# SCH_New-Project_2024-09-05.net
KiCad netlist of a schematic drawn in EasyEDA
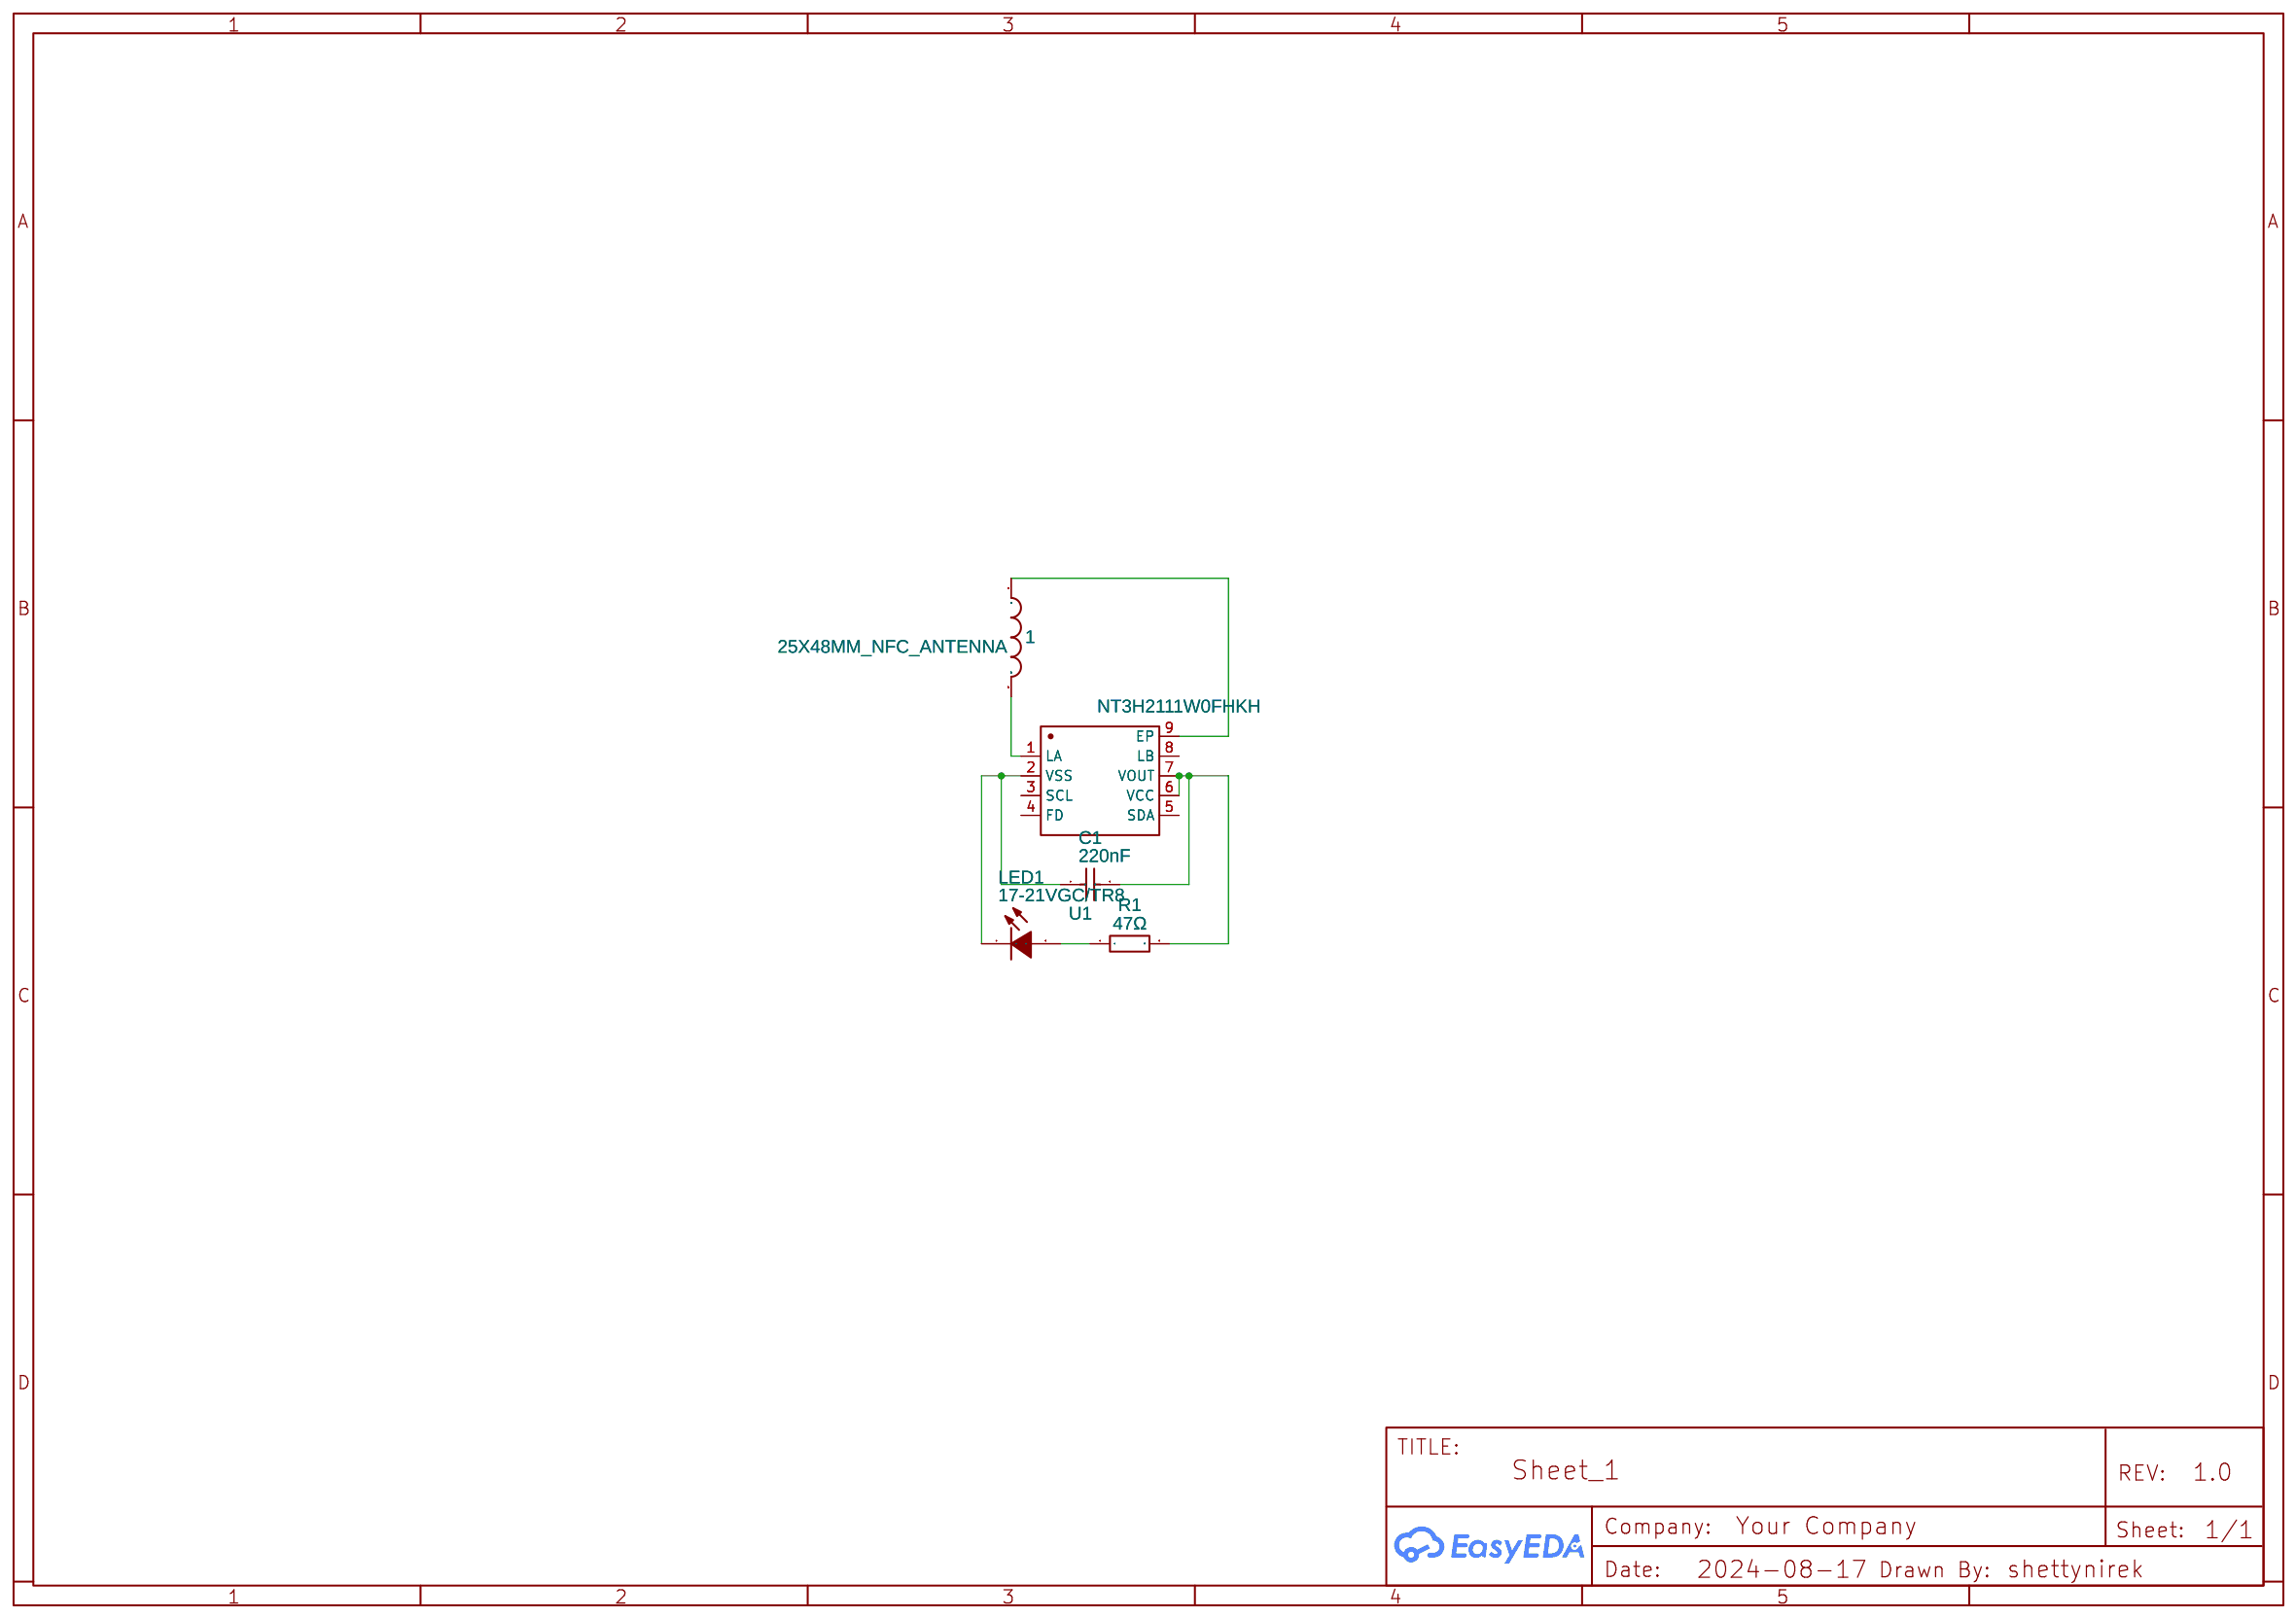
[diagram p0: schematic sheet]

(export (version "E")
  (design (tool "Eeschema 10.0.6"))
  (components
    (comp (ref "1") (value "25X48MM_NFC_ANTENNA") (libsource (lib "") (part "25X48MM_NFC_ANTENNA")))
    (comp (ref "C1")
      (value "220nF")
      (fields
        (field (name "Manufacturer Part") "CL10B224KA8NNNC")
        (field (name "Manufacturer") "SAMSUNG(三星)")
      )
      (libsource (lib "") (part "CL10B224KA8NNNC"))
    )
    (comp (ref "LED1")
      (value "17-21VGC/TR8")
      (fields (field (name "Manufacturer") "EVERLIGHT(亿光)"))
      (libsource (lib "") (part "17-21VGC/TR8"))
    )
    (comp (ref "R1")
      (value "47Ω")
      (fields
        (field (name "Manufacturer Part") "0603WAF470JT5E")
        (field (name "Manufacturer") "UNI-ROYAL(厚声)")
      )
      (libsource (lib "") (part "0603WAF470JT5E"))
    )
    (comp (ref "U1")
      (value "NT3H2111W0FHKH")
      (fields (field (name "Manufacturer") "NXP(恩智浦)"))
      (libsource (lib "") (part "NT3H2111W0FHKH"))
    )
  )
  (nets
    (net (code "1") (name "Net-(LED1-+)") (class "Default")
      (node (ref "LED1") (pin "2") (pinfunction "+_2") (pintype "unspecified"))
      (node (ref "R1") (pin "1") (pinfunction "1_1") (pintype "input"))
    )
    (net (code "2") (name "Net-(LED1--)") (class "Default")
      (node (ref "C1") (pin "1") (pinfunction "1_1") (pintype "input"))
      (node (ref "LED1") (pin "1") (pinfunction "-_1") (pintype "unspecified"))
      (node (ref "U1") (pin "2") (pinfunction "VSS_2") (pintype "unspecified"))
    )
    (net (code "3") (name "Net-(U1-EP)") (class "Default")
      (node (ref "1") (pin "P$1") (pinfunction "P$1_P$1") (pintype "bidirectional"))
      (node (ref "U1") (pin "9") (pinfunction "EP_9") (pintype "unspecified"))
    )
    (net (code "4") (name "Net-(U1-LA)") (class "Default")
      (node (ref "1") (pin "P$2") (pinfunction "P$2_P$2") (pintype "bidirectional"))
      (node (ref "U1") (pin "1") (pinfunction "LA_1") (pintype "unspecified"))
    )
    (net (code "5") (name "Net-(U1-VCC)") (class "Default")
      (node (ref "C1") (pin "2") (pinfunction "2_2") (pintype "input"))
      (node (ref "R1") (pin "2") (pinfunction "2_2") (pintype "input"))
      (node (ref "U1") (pin "6") (pinfunction "VCC_6") (pintype "unspecified"))
      (node (ref "U1") (pin "7") (pinfunction "VOUT_7") (pintype "unspecified"))
    )
    (net (code "6") (name "unconnected-(U1-FD-Pad4)") (class "Default")
      (node (ref "U1") (pin "4") (pinfunction "FD_4") (pintype "unspecified"))
    )
    (net (code "7") (name "unconnected-(U1-LB-Pad8)") (class "Default")
      (node (ref "U1") (pin "8") (pinfunction "LB_8") (pintype "unspecified"))
    )
    (net (code "8") (name "unconnected-(U1-SCL-Pad3)") (class "Default")
      (node (ref "U1") (pin "3") (pinfunction "SCL_3") (pintype "unspecified"))
    )
    (net (code "9") (name "unconnected-(U1-SDA-Pad5)") (class "Default")
      (node (ref "U1") (pin "5") (pinfunction "SDA_5") (pintype "unspecified"))
    )
  )
)
